# TEST_BTB.net
KiCad netlist of a schematic drawn in Altium Designer
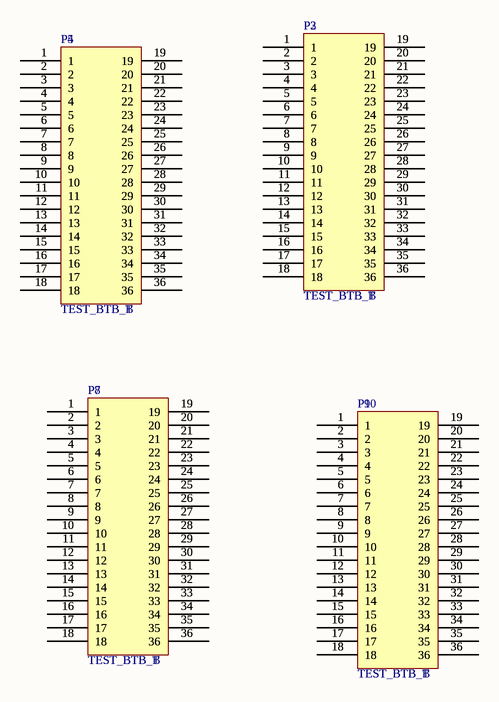
[diagram p0: TEST_BTB.SchDoc]

(export (version "E")
  (design (tool "Eeschema 10.0.6"))
  (components
    (comp (ref "P2")
      (value "TEST_BTB_T")
      (footprint "TEST_BTB_T")
      (libsource (lib "mcu") (part "TEST_BTB_T"))
    )
    (comp (ref "P3")
      (value "TEST_BTB_B")
      (footprint "TEST_BTB_B")
      (libsource (lib "mcu") (part "TEST_BTB_B"))
    )
    (comp (ref "P4")
      (value "TEST_BTB_T")
      (footprint "TEST_BTB_T")
      (libsource (lib "mcu") (part "TEST_BTB_T"))
    )
    (comp (ref "P5")
      (value "TEST_BTB_B")
      (footprint "TEST_BTB_B")
      (libsource (lib "mcu") (part "TEST_BTB_B"))
    )
    (comp (ref "P7")
      (value "TEST_BTB_B")
      (footprint "TEST_BTB_B")
      (libsource (lib "mcu") (part "TEST_BTB_B"))
    )
    (comp (ref "P8")
      (value "TEST_BTB_T")
      (footprint "TEST_BTB_T")
      (libsource (lib "mcu") (part "TEST_BTB_T"))
    )
    (comp (ref "P9")
      (value "TEST_BTB_B")
      (footprint "TEST_BTB_B")
      (libsource (lib "mcu") (part "TEST_BTB_B"))
    )
    (comp (ref "P10")
      (value "TEST_BTB_T")
      (footprint "TEST_BTB_T")
      (libsource (lib "mcu") (part "TEST_BTB_T"))
    )
  )
  (nets
    (net (code "1") (name "Net-(P2-Pad1)") (class "Default")
      (node (ref "P2") (pin "1") (pinfunction "1_1") (pintype "passive"))
      (node (ref "P3") (pin "1") (pinfunction "1_1") (pintype "passive"))
    )
    (net (code "2") (name "Net-(P2-Pad2)") (class "Default")
      (node (ref "P2") (pin "2") (pinfunction "2_2") (pintype "passive"))
      (node (ref "P3") (pin "2") (pinfunction "2_2") (pintype "passive"))
    )
    (net (code "3") (name "Net-(P2-Pad3)") (class "Default")
      (node (ref "P2") (pin "3") (pinfunction "3_3") (pintype "passive"))
      (node (ref "P3") (pin "3") (pinfunction "3_3") (pintype "passive"))
    )
    (net (code "4") (name "Net-(P2-Pad4)") (class "Default")
      (node (ref "P2") (pin "4") (pinfunction "4_4") (pintype "passive"))
      (node (ref "P3") (pin "4") (pinfunction "4_4") (pintype "passive"))
    )
    (net (code "5") (name "Net-(P2-Pad5)") (class "Default")
      (node (ref "P2") (pin "5") (pinfunction "5_5") (pintype "passive"))
      (node (ref "P3") (pin "5") (pinfunction "5_5") (pintype "passive"))
    )
    (net (code "6") (name "Net-(P2-Pad6)") (class "Default")
      (node (ref "P2") (pin "6") (pinfunction "6_6") (pintype "passive"))
      (node (ref "P3") (pin "6") (pinfunction "6_6") (pintype "passive"))
    )
    (net (code "7") (name "Net-(P2-Pad7)") (class "Default")
      (node (ref "P2") (pin "7") (pinfunction "7_7") (pintype "passive"))
      (node (ref "P3") (pin "7") (pinfunction "7_7") (pintype "passive"))
    )
    (net (code "8") (name "Net-(P2-Pad8)") (class "Default")
      (node (ref "P2") (pin "8") (pinfunction "8_8") (pintype "passive"))
      (node (ref "P3") (pin "8") (pinfunction "8_8") (pintype "passive"))
    )
    (net (code "9") (name "Net-(P2-Pad9)") (class "Default")
      (node (ref "P2") (pin "9") (pinfunction "9_9") (pintype "passive"))
      (node (ref "P3") (pin "9") (pinfunction "9_9") (pintype "passive"))
    )
    (net (code "10") (name "Net-(P2-Pad10)") (class "Default")
      (node (ref "P2") (pin "10") (pinfunction "10_10") (pintype "passive"))
      (node (ref "P3") (pin "10") (pinfunction "10_10") (pintype "passive"))
    )
    (net (code "11") (name "Net-(P2-Pad11)") (class "Default")
      (node (ref "P2") (pin "11") (pinfunction "11_11") (pintype "passive"))
      (node (ref "P3") (pin "11") (pinfunction "11_11") (pintype "passive"))
    )
    (net (code "12") (name "Net-(P2-Pad12)") (class "Default")
      (node (ref "P2") (pin "12") (pinfunction "12_12") (pintype "passive"))
      (node (ref "P3") (pin "12") (pinfunction "12_12") (pintype "passive"))
    )
    (net (code "13") (name "Net-(P2-Pad13)") (class "Default")
      (node (ref "P2") (pin "13") (pinfunction "13_13") (pintype "passive"))
      (node (ref "P3") (pin "13") (pinfunction "13_13") (pintype "passive"))
    )
    (net (code "14") (name "Net-(P2-Pad14)") (class "Default")
      (node (ref "P2") (pin "14") (pinfunction "14_14") (pintype "passive"))
      (node (ref "P3") (pin "14") (pinfunction "14_14") (pintype "passive"))
    )
    (net (code "15") (name "Net-(P2-Pad15)") (class "Default")
      (node (ref "P2") (pin "15") (pinfunction "15_15") (pintype "passive"))
      (node (ref "P3") (pin "15") (pinfunction "15_15") (pintype "passive"))
    )
    (net (code "16") (name "Net-(P2-Pad16)") (class "Default")
      (node (ref "P2") (pin "16") (pinfunction "16_16") (pintype "passive"))
      (node (ref "P3") (pin "16") (pinfunction "16_16") (pintype "passive"))
    )
    (net (code "17") (name "Net-(P2-Pad17)") (class "Default")
      (node (ref "P2") (pin "17") (pinfunction "17_17") (pintype "passive"))
      (node (ref "P3") (pin "17") (pinfunction "17_17") (pintype "passive"))
    )
    (net (code "18") (name "Net-(P2-Pad18)") (class "Default")
      (node (ref "P2") (pin "18") (pinfunction "18_18") (pintype "passive"))
      (node (ref "P3") (pin "18") (pinfunction "18_18") (pintype "passive"))
    )
    (net (code "19") (name "Net-(P2-Pad19)") (class "Default")
      (node (ref "P2") (pin "19") (pinfunction "19_19") (pintype "passive"))
      (node (ref "P3") (pin "19") (pinfunction "19_19") (pintype "passive"))
    )
    (net (code "20") (name "Net-(P2-Pad20)") (class "Default")
      (node (ref "P2") (pin "20") (pinfunction "20_20") (pintype "passive"))
      (node (ref "P3") (pin "20") (pinfunction "20_20") (pintype "passive"))
    )
    (net (code "21") (name "Net-(P2-Pad21)") (class "Default")
      (node (ref "P2") (pin "21") (pinfunction "21_21") (pintype "passive"))
      (node (ref "P3") (pin "21") (pinfunction "21_21") (pintype "passive"))
    )
    (net (code "22") (name "Net-(P2-Pad22)") (class "Default")
      (node (ref "P2") (pin "22") (pinfunction "22_22") (pintype "passive"))
      (node (ref "P3") (pin "22") (pinfunction "22_22") (pintype "passive"))
    )
    (net (code "23") (name "Net-(P2-Pad23)") (class "Default")
      (node (ref "P2") (pin "23") (pinfunction "23_23") (pintype "passive"))
      (node (ref "P3") (pin "23") (pinfunction "23_23") (pintype "passive"))
    )
    (net (code "24") (name "Net-(P2-Pad24)") (class "Default")
      (node (ref "P2") (pin "24") (pinfunction "24_24") (pintype "passive"))
      (node (ref "P3") (pin "24") (pinfunction "24_24") (pintype "passive"))
    )
    (net (code "25") (name "Net-(P2-Pad25)") (class "Default")
      (node (ref "P2") (pin "25") (pinfunction "25_25") (pintype "passive"))
      (node (ref "P3") (pin "25") (pinfunction "25_25") (pintype "passive"))
    )
    (net (code "26") (name "Net-(P2-Pad26)") (class "Default")
      (node (ref "P2") (pin "26") (pinfunction "26_26") (pintype "passive"))
      (node (ref "P3") (pin "26") (pinfunction "26_26") (pintype "passive"))
    )
    (net (code "27") (name "Net-(P2-Pad27)") (class "Default")
      (node (ref "P2") (pin "27") (pinfunction "27_27") (pintype "passive"))
      (node (ref "P3") (pin "27") (pinfunction "27_27") (pintype "passive"))
    )
    (net (code "28") (name "Net-(P2-Pad28)") (class "Default")
      (node (ref "P2") (pin "28") (pinfunction "28_28") (pintype "passive"))
      (node (ref "P3") (pin "28") (pinfunction "28_28") (pintype "passive"))
    )
    (net (code "29") (name "Net-(P2-Pad29)") (class "Default")
      (node (ref "P2") (pin "29") (pinfunction "29_29") (pintype "passive"))
      (node (ref "P3") (pin "29") (pinfunction "29_29") (pintype "passive"))
    )
    (net (code "30") (name "Net-(P2-Pad30)") (class "Default")
      (node (ref "P2") (pin "30") (pinfunction "30_30") (pintype "passive"))
      (node (ref "P3") (pin "30") (pinfunction "30_30") (pintype "passive"))
    )
    (net (code "31") (name "Net-(P2-Pad31)") (class "Default")
      (node (ref "P2") (pin "31") (pinfunction "31_31") (pintype "passive"))
      (node (ref "P3") (pin "31") (pinfunction "31_31") (pintype "passive"))
    )
    (net (code "32") (name "Net-(P2-Pad32)") (class "Default")
      (node (ref "P2") (pin "32") (pinfunction "32_32") (pintype "passive"))
      (node (ref "P3") (pin "32") (pinfunction "32_32") (pintype "passive"))
    )
    (net (code "33") (name "Net-(P2-Pad33)") (class "Default")
      (node (ref "P2") (pin "33") (pinfunction "33_33") (pintype "passive"))
      (node (ref "P3") (pin "33") (pinfunction "33_33") (pintype "passive"))
    )
    (net (code "34") (name "Net-(P2-Pad34)") (class "Default")
      (node (ref "P2") (pin "34") (pinfunction "34_34") (pintype "passive"))
      (node (ref "P3") (pin "34") (pinfunction "34_34") (pintype "passive"))
    )
    (net (code "35") (name "Net-(P2-Pad35)") (class "Default")
      (node (ref "P2") (pin "35") (pinfunction "35_35") (pintype "passive"))
      (node (ref "P3") (pin "35") (pinfunction "35_35") (pintype "passive"))
    )
    (net (code "36") (name "Net-(P2-Pad36)") (class "Default")
      (node (ref "P2") (pin "36") (pinfunction "36_36") (pintype "passive"))
      (node (ref "P3") (pin "36") (pinfunction "36_36") (pintype "passive"))
    )
    (net (code "37") (name "Net-(P4-Pad1)") (class "Default")
      (node (ref "P4") (pin "1") (pinfunction "1_1") (pintype "passive"))
      (node (ref "P5") (pin "1") (pinfunction "1_1") (pintype "passive"))
    )
    (net (code "38") (name "Net-(P4-Pad2)") (class "Default")
      (node (ref "P4") (pin "2") (pinfunction "2_2") (pintype "passive"))
      (node (ref "P5") (pin "2") (pinfunction "2_2") (pintype "passive"))
    )
    (net (code "39") (name "Net-(P4-Pad3)") (class "Default")
      (node (ref "P4") (pin "3") (pinfunction "3_3") (pintype "passive"))
      (node (ref "P5") (pin "3") (pinfunction "3_3") (pintype "passive"))
    )
    (net (code "40") (name "Net-(P4-Pad4)") (class "Default")
      (node (ref "P4") (pin "4") (pinfunction "4_4") (pintype "passive"))
      (node (ref "P5") (pin "4") (pinfunction "4_4") (pintype "passive"))
    )
    (net (code "41") (name "Net-(P4-Pad5)") (class "Default")
      (node (ref "P4") (pin "5") (pinfunction "5_5") (pintype "passive"))
      (node (ref "P5") (pin "5") (pinfunction "5_5") (pintype "passive"))
    )
    (net (code "42") (name "Net-(P4-Pad6)") (class "Default")
      (node (ref "P4") (pin "6") (pinfunction "6_6") (pintype "passive"))
      (node (ref "P5") (pin "6") (pinfunction "6_6") (pintype "passive"))
    )
    (net (code "43") (name "Net-(P4-Pad7)") (class "Default")
      (node (ref "P4") (pin "7") (pinfunction "7_7") (pintype "passive"))
      (node (ref "P5") (pin "7") (pinfunction "7_7") (pintype "passive"))
    )
    (net (code "44") (name "Net-(P4-Pad8)") (class "Default")
      (node (ref "P4") (pin "8") (pinfunction "8_8") (pintype "passive"))
      (node (ref "P5") (pin "8") (pinfunction "8_8") (pintype "passive"))
    )
    (net (code "45") (name "Net-(P4-Pad9)") (class "Default")
      (node (ref "P4") (pin "9") (pinfunction "9_9") (pintype "passive"))
      (node (ref "P5") (pin "9") (pinfunction "9_9") (pintype "passive"))
    )
    (net (code "46") (name "Net-(P4-Pad10)") (class "Default")
      (node (ref "P4") (pin "10") (pinfunction "10_10") (pintype "passive"))
      (node (ref "P5") (pin "10") (pinfunction "10_10") (pintype "passive"))
    )
    (net (code "47") (name "Net-(P4-Pad11)") (class "Default")
      (node (ref "P4") (pin "11") (pinfunction "11_11") (pintype "passive"))
      (node (ref "P5") (pin "11") (pinfunction "11_11") (pintype "passive"))
    )
    (net (code "48") (name "Net-(P4-Pad12)") (class "Default")
      (node (ref "P4") (pin "12") (pinfunction "12_12") (pintype "passive"))
      (node (ref "P5") (pin "12") (pinfunction "12_12") (pintype "passive"))
    )
    (net (code "49") (name "Net-(P4-Pad13)") (class "Default")
      (node (ref "P4") (pin "13") (pinfunction "13_13") (pintype "passive"))
      (node (ref "P5") (pin "13") (pinfunction "13_13") (pintype "passive"))
    )
    (net (code "50") (name "Net-(P4-Pad14)") (class "Default")
      (node (ref "P4") (pin "14") (pinfunction "14_14") (pintype "passive"))
      (node (ref "P5") (pin "14") (pinfunction "14_14") (pintype "passive"))
    )
    (net (code "51") (name "Net-(P4-Pad15)") (class "Default")
      (node (ref "P4") (pin "15") (pinfunction "15_15") (pintype "passive"))
      (node (ref "P5") (pin "15") (pinfunction "15_15") (pintype "passive"))
    )
    (net (code "52") (name "Net-(P4-Pad16)") (class "Default")
      (node (ref "P4") (pin "16") (pinfunction "16_16") (pintype "passive"))
      (node (ref "P5") (pin "16") (pinfunction "16_16") (pintype "passive"))
    )
    (net (code "53") (name "Net-(P4-Pad17)") (class "Default")
      (node (ref "P4") (pin "17") (pinfunction "17_17") (pintype "passive"))
      (node (ref "P5") (pin "17") (pinfunction "17_17") (pintype "passive"))
    )
    (net (code "54") (name "Net-(P4-Pad18)") (class "Default")
      (node (ref "P4") (pin "18") (pinfunction "18_18") (pintype "passive"))
      (node (ref "P5") (pin "18") (pinfunction "18_18") (pintype "passive"))
    )
    (net (code "55") (name "Net-(P4-Pad19)") (class "Default")
      (node (ref "P4") (pin "19") (pinfunction "19_19") (pintype "passive"))
      (node (ref "P5") (pin "19") (pinfunction "19_19") (pintype "passive"))
    )
    (net (code "56") (name "Net-(P4-Pad20)") (class "Default")
      (node (ref "P4") (pin "20") (pinfunction "20_20") (pintype "passive"))
      (node (ref "P5") (pin "20") (pinfunction "20_20") (pintype "passive"))
    )
    (net (code "57") (name "Net-(P4-Pad21)") (class "Default")
      (node (ref "P4") (pin "21") (pinfunction "21_21") (pintype "passive"))
      (node (ref "P5") (pin "21") (pinfunction "21_21") (pintype "passive"))
    )
    (net (code "58") (name "Net-(P4-Pad22)") (class "Default")
      (node (ref "P4") (pin "22") (pinfunction "22_22") (pintype "passive"))
      (node (ref "P5") (pin "22") (pinfunction "22_22") (pintype "passive"))
    )
    (net (code "59") (name "Net-(P4-Pad23)") (class "Default")
      (node (ref "P4") (pin "23") (pinfunction "23_23") (pintype "passive"))
      (node (ref "P5") (pin "23") (pinfunction "23_23") (pintype "passive"))
    )
    (net (code "60") (name "Net-(P4-Pad24)") (class "Default")
      (node (ref "P4") (pin "24") (pinfunction "24_24") (pintype "passive"))
      (node (ref "P5") (pin "24") (pinfunction "24_24") (pintype "passive"))
    )
    (net (code "61") (name "Net-(P4-Pad25)") (class "Default")
      (node (ref "P4") (pin "25") (pinfunction "25_25") (pintype "passive"))
      (node (ref "P5") (pin "25") (pinfunction "25_25") (pintype "passive"))
    )
    (net (code "62") (name "Net-(P4-Pad26)") (class "Default")
      (node (ref "P4") (pin "26") (pinfunction "26_26") (pintype "passive"))
      (node (ref "P5") (pin "26") (pinfunction "26_26") (pintype "passive"))
    )
    (net (code "63") (name "Net-(P4-Pad27)") (class "Default")
      (node (ref "P4") (pin "27") (pinfunction "27_27") (pintype "passive"))
      (node (ref "P5") (pin "27") (pinfunction "27_27") (pintype "passive"))
    )
    (net (code "64") (name "Net-(P4-Pad28)") (class "Default")
      (node (ref "P4") (pin "28") (pinfunction "28_28") (pintype "passive"))
      (node (ref "P5") (pin "28") (pinfunction "28_28") (pintype "passive"))
    )
    (net (code "65") (name "Net-(P4-Pad29)") (class "Default")
      (node (ref "P4") (pin "29") (pinfunction "29_29") (pintype "passive"))
      (node (ref "P5") (pin "29") (pinfunction "29_29") (pintype "passive"))
    )
    (net (code "66") (name "Net-(P4-Pad30)") (class "Default")
      (node (ref "P4") (pin "30") (pinfunction "30_30") (pintype "passive"))
      (node (ref "P5") (pin "30") (pinfunction "30_30") (pintype "passive"))
    )
    (net (code "67") (name "Net-(P4-Pad31)") (class "Default")
      (node (ref "P4") (pin "31") (pinfunction "31_31") (pintype "passive"))
      (node (ref "P5") (pin "31") (pinfunction "31_31") (pintype "passive"))
    )
    (net (code "68") (name "Net-(P4-Pad32)") (class "Default")
      (node (ref "P4") (pin "32") (pinfunction "32_32") (pintype "passive"))
      (node (ref "P5") (pin "32") (pinfunction "32_32") (pintype "passive"))
    )
    (net (code "69") (name "Net-(P4-Pad33)") (class "Default")
      (node (ref "P4") (pin "33") (pinfunction "33_33") (pintype "passive"))
      (node (ref "P5") (pin "33") (pinfunction "33_33") (pintype "passive"))
    )
    (net (code "70") (name "Net-(P4-Pad34)") (class "Default")
      (node (ref "P4") (pin "34") (pinfunction "34_34") (pintype "passive"))
      (node (ref "P5") (pin "34") (pinfunction "34_34") (pintype "passive"))
    )
    (net (code "71") (name "Net-(P4-Pad35)") (class "Default")
      (node (ref "P4") (pin "35") (pinfunction "35_35") (pintype "passive"))
      (node (ref "P5") (pin "35") (pinfunction "35_35") (pintype "passive"))
    )
    (net (code "72") (name "Net-(P4-Pad36)") (class "Default")
      (node (ref "P4") (pin "36") (pinfunction "36_36") (pintype "passive"))
      (node (ref "P5") (pin "36") (pinfunction "36_36") (pintype "passive"))
    )
    (net (code "73") (name "Net-(P7-Pad1)") (class "Default")
      (node (ref "P7") (pin "1") (pinfunction "1_1") (pintype "passive"))
      (node (ref "P8") (pin "1") (pinfunction "1_1") (pintype "passive"))
    )
    (net (code "74") (name "Net-(P7-Pad2)") (class "Default")
      (node (ref "P7") (pin "2") (pinfunction "2_2") (pintype "passive"))
      (node (ref "P8") (pin "2") (pinfunction "2_2") (pintype "passive"))
    )
    (net (code "75") (name "Net-(P7-Pad3)") (class "Default")
      (node (ref "P7") (pin "3") (pinfunction "3_3") (pintype "passive"))
      (node (ref "P8") (pin "3") (pinfunction "3_3") (pintype "passive"))
    )
    (net (code "76") (name "Net-(P7-Pad4)") (class "Default")
      (node (ref "P7") (pin "4") (pinfunction "4_4") (pintype "passive"))
      (node (ref "P8") (pin "4") (pinfunction "4_4") (pintype "passive"))
    )
    (net (code "77") (name "Net-(P7-Pad5)") (class "Default")
      (node (ref "P7") (pin "5") (pinfunction "5_5") (pintype "passive"))
      (node (ref "P8") (pin "5") (pinfunction "5_5") (pintype "passive"))
    )
    (net (code "78") (name "Net-(P7-Pad6)") (class "Default")
      (node (ref "P7") (pin "6") (pinfunction "6_6") (pintype "passive"))
      (node (ref "P8") (pin "6") (pinfunction "6_6") (pintype "passive"))
    )
    (net (code "79") (name "Net-(P7-Pad7)") (class "Default")
      (node (ref "P7") (pin "7") (pinfunction "7_7") (pintype "passive"))
      (node (ref "P8") (pin "7") (pinfunction "7_7") (pintype "passive"))
    )
    (net (code "80") (name "Net-(P7-Pad8)") (class "Default")
      (node (ref "P7") (pin "8") (pinfunction "8_8") (pintype "passive"))
      (node (ref "P8") (pin "8") (pinfunction "8_8") (pintype "passive"))
    )
    (net (code "81") (name "Net-(P7-Pad9)") (class "Default")
      (node (ref "P7") (pin "9") (pinfunction "9_9") (pintype "passive"))
      (node (ref "P8") (pin "9") (pinfunction "9_9") (pintype "passive"))
    )
    (net (code "82") (name "Net-(P7-Pad10)") (class "Default")
      (node (ref "P7") (pin "10") (pinfunction "10_10") (pintype "passive"))
      (node (ref "P8") (pin "10") (pinfunction "10_10") (pintype "passive"))
    )
    (net (code "83") (name "Net-(P7-Pad11)") (class "Default")
      (node (ref "P7") (pin "11") (pinfunction "11_11") (pintype "passive"))
      (node (ref "P8") (pin "11") (pinfunction "11_11") (pintype "passive"))
    )
    (net (code "84") (name "Net-(P7-Pad12)") (class "Default")
      (node (ref "P7") (pin "12") (pinfunction "12_12") (pintype "passive"))
      (node (ref "P8") (pin "12") (pinfunction "12_12") (pintype "passive"))
    )
    (net (code "85") (name "Net-(P7-Pad13)") (class "Default")
      (node (ref "P7") (pin "13") (pinfunction "13_13") (pintype "passive"))
      (node (ref "P8") (pin "13") (pinfunction "13_13") (pintype "passive"))
    )
    (net (code "86") (name "Net-(P7-Pad14)") (class "Default")
      (node (ref "P7") (pin "14") (pinfunction "14_14") (pintype "passive"))
      (node (ref "P8") (pin "14") (pinfunction "14_14") (pintype "passive"))
    )
    (net (code "87") (name "Net-(P7-Pad15)") (class "Default")
      (node (ref "P7") (pin "15") (pinfunction "15_15") (pintype "passive"))
      (node (ref "P8") (pin "15") (pinfunction "15_15") (pintype "passive"))
    )
    (net (code "88") (name "Net-(P7-Pad16)") (class "Default")
      (node (ref "P7") (pin "16") (pinfunction "16_16") (pintype "passive"))
      (node (ref "P8") (pin "16") (pinfunction "16_16") (pintype "passive"))
    )
    (net (code "89") (name "Net-(P7-Pad17)") (class "Default")
      (node (ref "P7") (pin "17") (pinfunction "17_17") (pintype "passive"))
      (node (ref "P8") (pin "17") (pinfunction "17_17") (pintype "passive"))
    )
    (net (code "90") (name "Net-(P7-Pad18)") (class "Default")
      (node (ref "P7") (pin "18") (pinfunction "18_18") (pintype "passive"))
      (node (ref "P8") (pin "18") (pinfunction "18_18") (pintype "passive"))
    )
    (net (code "91") (name "Net-(P7-Pad19)") (class "Default")
      (node (ref "P7") (pin "19") (pinfunction "19_19") (pintype "passive"))
      (node (ref "P8") (pin "19") (pinfunction "19_19") (pintype "passive"))
    )
    (net (code "92") (name "Net-(P7-Pad20)") (class "Default")
      (node (ref "P7") (pin "20") (pinfunction "20_20") (pintype "passive"))
      (node (ref "P8") (pin "20") (pinfunction "20_20") (pintype "passive"))
    )
    (net (code "93") (name "Net-(P7-Pad21)") (class "Default")
      (node (ref "P7") (pin "21") (pinfunction "21_21") (pintype "passive"))
      (node (ref "P8") (pin "21") (pinfunction "21_21") (pintype "passive"))
    )
    (net (code "94") (name "Net-(P7-Pad22)") (class "Default")
      (node (ref "P7") (pin "22") (pinfunction "22_22") (pintype "passive"))
      (node (ref "P8") (pin "22") (pinfunction "22_22") (pintype "passive"))
    )
    (net (code "95") (name "Net-(P7-Pad23)") (class "Default")
      (node (ref "P7") (pin "23") (pinfunction "23_23") (pintype "passive"))
      (node (ref "P8") (pin "23") (pinfunction "23_23") (pintype "passive"))
    )
    (net (code "96") (name "Net-(P7-Pad24)") (class "Default")
      (node (ref "P7") (pin "24") (pinfunction "24_24") (pintype "passive"))
      (node (ref "P8") (pin "24") (pinfunction "24_24") (pintype "passive"))
    )
    (net (code "97") (name "Net-(P7-Pad25)") (class "Default")
      (node (ref "P7") (pin "25") (pinfunction "25_25") (pintype "passive"))
      (node (ref "P8") (pin "25") (pinfunction "25_25") (pintype "passive"))
    )
    (net (code "98") (name "Net-(P7-Pad26)") (class "Default")
      (node (ref "P7") (pin "26") (pinfunction "26_26") (pintype "passive"))
      (node (ref "P8") (pin "26") (pinfunction "26_26") (pintype "passive"))
    )
    (net (code "99") (name "Net-(P7-Pad27)") (class "Default")
      (node (ref "P7") (pin "27") (pinfunction "27_27") (pintype "passive"))
      (node (ref "P8") (pin "27") (pinfunction "27_27") (pintype "passive"))
    )
    (net (code "100") (name "Net-(P7-Pad28)") (class "Default")
      (node (ref "P7") (pin "28") (pinfunction "28_28") (pintype "passive"))
      (node (ref "P8") (pin "28") (pinfunction "28_28") (pintype "passive"))
    )
    (net (code "101") (name "Net-(P7-Pad29)") (class "Default")
      (node (ref "P7") (pin "29") (pinfunction "29_29") (pintype "passive"))
      (node (ref "P8") (pin "29") (pinfunction "29_29") (pintype "passive"))
    )
    (net (code "102") (name "Net-(P7-Pad30)") (class "Default")
      (node (ref "P7") (pin "30") (pinfunction "30_30") (pintype "passive"))
      (node (ref "P8") (pin "30") (pinfunction "30_30") (pintype "passive"))
    )
    (net (code "103") (name "Net-(P7-Pad31)") (class "Default")
      (node (ref "P7") (pin "31") (pinfunction "31_31") (pintype "passive"))
      (node (ref "P8") (pin "31") (pinfunction "31_31") (pintype "passive"))
    )
    (net (code "104") (name "Net-(P7-Pad32)") (class "Default")
      (node (ref "P7") (pin "32") (pinfunction "32_32") (pintype "passive"))
      (node (ref "P8") (pin "32") (pinfunction "32_32") (pintype "passive"))
    )
    (net (code "105") (name "Net-(P7-Pad33)") (class "Default")
      (node (ref "P7") (pin "33") (pinfunction "33_33") (pintype "passive"))
      (node (ref "P8") (pin "33") (pinfunction "33_33") (pintype "passive"))
    )
    (net (code "106") (name "Net-(P7-Pad34)") (class "Default")
      (node (ref "P7") (pin "34") (pinfunction "34_34") (pintype "passive"))
      (node (ref "P8") (pin "34") (pinfunction "34_34") (pintype "passive"))
    )
    (net (code "107") (name "Net-(P7-Pad35)") (class "Default")
      (node (ref "P7") (pin "35") (pinfunction "35_35") (pintype "passive"))
      (node (ref "P8") (pin "35") (pinfunction "35_35") (pintype "passive"))
    )
    (net (code "108") (name "Net-(P7-Pad36)") (class "Default")
      (node (ref "P7") (pin "36") (pinfunction "36_36") (pintype "passive"))
      (node (ref "P8") (pin "36") (pinfunction "36_36") (pintype "passive"))
    )
    (net (code "109") (name "Net-(P10-Pad1)") (class "Default")
      (node (ref "P10") (pin "1") (pinfunction "1_1") (pintype "passive"))
      (node (ref "P9") (pin "1") (pinfunction "1_1") (pintype "passive"))
    )
    (net (code "110") (name "Net-(P10-Pad2)") (class "Default")
      (node (ref "P10") (pin "2") (pinfunction "2_2") (pintype "passive"))
      (node (ref "P9") (pin "2") (pinfunction "2_2") (pintype "passive"))
    )
    (net (code "111") (name "Net-(P10-Pad3)") (class "Default")
      (node (ref "P10") (pin "3") (pinfunction "3_3") (pintype "passive"))
      (node (ref "P9") (pin "3") (pinfunction "3_3") (pintype "passive"))
    )
    (net (code "112") (name "Net-(P10-Pad4)") (class "Default")
      (node (ref "P10") (pin "4") (pinfunction "4_4") (pintype "passive"))
      (node (ref "P9") (pin "4") (pinfunction "4_4") (pintype "passive"))
    )
    (net (code "113") (name "Net-(P10-Pad5)") (class "Default")
      (node (ref "P10") (pin "5") (pinfunction "5_5") (pintype "passive"))
      (node (ref "P9") (pin "5") (pinfunction "5_5") (pintype "passive"))
    )
    (net (code "114") (name "Net-(P10-Pad6)") (class "Default")
      (node (ref "P10") (pin "6") (pinfunction "6_6") (pintype "passive"))
      (node (ref "P9") (pin "6") (pinfunction "6_6") (pintype "passive"))
    )
    (net (code "115") (name "Net-(P10-Pad7)") (class "Default")
      (node (ref "P10") (pin "7") (pinfunction "7_7") (pintype "passive"))
      (node (ref "P9") (pin "7") (pinfunction "7_7") (pintype "passive"))
    )
    (net (code "116") (name "Net-(P10-Pad8)") (class "Default")
      (node (ref "P10") (pin "8") (pinfunction "8_8") (pintype "passive"))
      (node (ref "P9") (pin "8") (pinfunction "8_8") (pintype "passive"))
    )
    (net (code "117") (name "Net-(P10-Pad9)") (class "Default")
      (node (ref "P10") (pin "9") (pinfunction "9_9") (pintype "passive"))
      (node (ref "P9") (pin "9") (pinfunction "9_9") (pintype "passive"))
    )
    (net (code "118") (name "Net-(P10-Pad10)") (class "Default")
      (node (ref "P10") (pin "10") (pinfunction "10_10") (pintype "passive"))
      (node (ref "P9") (pin "10") (pinfunction "10_10") (pintype "passive"))
    )
    (net (code "119") (name "Net-(P10-Pad11)") (class "Default")
      (node (ref "P10") (pin "11") (pinfunction "11_11") (pintype "passive"))
      (node (ref "P9") (pin "11") (pinfunction "11_11") (pintype "passive"))
    )
    (net (code "120") (name "Net-(P10-Pad12)") (class "Default")
      (node (ref "P10") (pin "12") (pinfunction "12_12") (pintype "passive"))
      (node (ref "P9") (pin "12") (pinfunction "12_12") (pintype "passive"))
    )
    (net (code "121") (name "Net-(P10-Pad13)") (class "Default")
      (node (ref "P10") (pin "13") (pinfunction "13_13") (pintype "passive"))
      (node (ref "P9") (pin "13") (pinfunction "13_13") (pintype "passive"))
    )
    (net (code "122") (name "Net-(P10-Pad14)") (class "Default")
      (node (ref "P10") (pin "14") (pinfunction "14_14") (pintype "passive"))
      (node (ref "P9") (pin "14") (pinfunction "14_14") (pintype "passive"))
    )
    (net (code "123") (name "Net-(P10-Pad15)") (class "Default")
      (node (ref "P10") (pin "15") (pinfunction "15_15") (pintype "passive"))
      (node (ref "P9") (pin "15") (pinfunction "15_15") (pintype "passive"))
    )
    (net (code "124") (name "Net-(P10-Pad16)") (class "Default")
      (node (ref "P10") (pin "16") (pinfunction "16_16") (pintype "passive"))
      (node (ref "P9") (pin "16") (pinfunction "16_16") (pintype "passive"))
    )
    (net (code "125") (name "Net-(P10-Pad17)") (class "Default")
      (node (ref "P10") (pin "17") (pinfunction "17_17") (pintype "passive"))
      (node (ref "P9") (pin "17") (pinfunction "17_17") (pintype "passive"))
    )
    (net (code "126") (name "Net-(P10-Pad18)") (class "Default")
      (node (ref "P10") (pin "18") (pinfunction "18_18") (pintype "passive"))
      (node (ref "P9") (pin "18") (pinfunction "18_18") (pintype "passive"))
    )
    (net (code "127") (name "Net-(P10-Pad19)") (class "Default")
      (node (ref "P10") (pin "19") (pinfunction "19_19") (pintype "passive"))
      (node (ref "P9") (pin "19") (pinfunction "19_19") (pintype "passive"))
    )
    (net (code "128") (name "Net-(P10-Pad20)") (class "Default")
      (node (ref "P10") (pin "20") (pinfunction "20_20") (pintype "passive"))
      (node (ref "P9") (pin "20") (pinfunction "20_20") (pintype "passive"))
    )
    (net (code "129") (name "Net-(P10-Pad21)") (class "Default")
      (node (ref "P10") (pin "21") (pinfunction "21_21") (pintype "passive"))
      (node (ref "P9") (pin "21") (pinfunction "21_21") (pintype "passive"))
    )
    (net (code "130") (name "Net-(P10-Pad22)") (class "Default")
      (node (ref "P10") (pin "22") (pinfunction "22_22") (pintype "passive"))
      (node (ref "P9") (pin "22") (pinfunction "22_22") (pintype "passive"))
    )
    (net (code "131") (name "Net-(P10-Pad23)") (class "Default")
      (node (ref "P10") (pin "23") (pinfunction "23_23") (pintype "passive"))
      (node (ref "P9") (pin "23") (pinfunction "23_23") (pintype "passive"))
    )
    (net (code "132") (name "Net-(P10-Pad24)") (class "Default")
      (node (ref "P10") (pin "24") (pinfunction "24_24") (pintype "passive"))
      (node (ref "P9") (pin "24") (pinfunction "24_24") (pintype "passive"))
    )
    (net (code "133") (name "Net-(P10-Pad25)") (class "Default")
      (node (ref "P10") (pin "25") (pinfunction "25_25") (pintype "passive"))
      (node (ref "P9") (pin "25") (pinfunction "25_25") (pintype "passive"))
    )
    (net (code "134") (name "Net-(P10-Pad26)") (class "Default")
      (node (ref "P10") (pin "26") (pinfunction "26_26") (pintype "passive"))
      (node (ref "P9") (pin "26") (pinfunction "26_26") (pintype "passive"))
    )
    (net (code "135") (name "Net-(P10-Pad27)") (class "Default")
      (node (ref "P10") (pin "27") (pinfunction "27_27") (pintype "passive"))
      (node (ref "P9") (pin "27") (pinfunction "27_27") (pintype "passive"))
    )
    (net (code "136") (name "Net-(P10-Pad28)") (class "Default")
      (node (ref "P10") (pin "28") (pinfunction "28_28") (pintype "passive"))
      (node (ref "P9") (pin "28") (pinfunction "28_28") (pintype "passive"))
    )
    (net (code "137") (name "Net-(P10-Pad29)") (class "Default")
      (node (ref "P10") (pin "29") (pinfunction "29_29") (pintype "passive"))
      (node (ref "P9") (pin "29") (pinfunction "29_29") (pintype "passive"))
    )
    (net (code "138") (name "Net-(P10-Pad30)") (class "Default")
      (node (ref "P10") (pin "30") (pinfunction "30_30") (pintype "passive"))
      (node (ref "P9") (pin "30") (pinfunction "30_30") (pintype "passive"))
    )
    (net (code "139") (name "Net-(P10-Pad31)") (class "Default")
      (node (ref "P10") (pin "31") (pinfunction "31_31") (pintype "passive"))
      (node (ref "P9") (pin "31") (pinfunction "31_31") (pintype "passive"))
    )
    (net (code "140") (name "Net-(P10-Pad32)") (class "Default")
      (node (ref "P10") (pin "32") (pinfunction "32_32") (pintype "passive"))
      (node (ref "P9") (pin "32") (pinfunction "32_32") (pintype "passive"))
    )
    (net (code "141") (name "Net-(P10-Pad33)") (class "Default")
      (node (ref "P10") (pin "33") (pinfunction "33_33") (pintype "passive"))
      (node (ref "P9") (pin "33") (pinfunction "33_33") (pintype "passive"))
    )
    (net (code "142") (name "Net-(P10-Pad34)") (class "Default")
      (node (ref "P10") (pin "34") (pinfunction "34_34") (pintype "passive"))
      (node (ref "P9") (pin "34") (pinfunction "34_34") (pintype "passive"))
    )
    (net (code "143") (name "Net-(P10-Pad35)") (class "Default")
      (node (ref "P10") (pin "35") (pinfunction "35_35") (pintype "passive"))
      (node (ref "P9") (pin "35") (pinfunction "35_35") (pintype "passive"))
    )
    (net (code "144") (name "Net-(P10-Pad36)") (class "Default")
      (node (ref "P10") (pin "36") (pinfunction "36_36") (pintype "passive"))
      (node (ref "P9") (pin "36") (pinfunction "36_36") (pintype "passive"))
    )
  )
)
